# PCBMotores.net
KiCad netlist of a schematic drawn in EAGLE
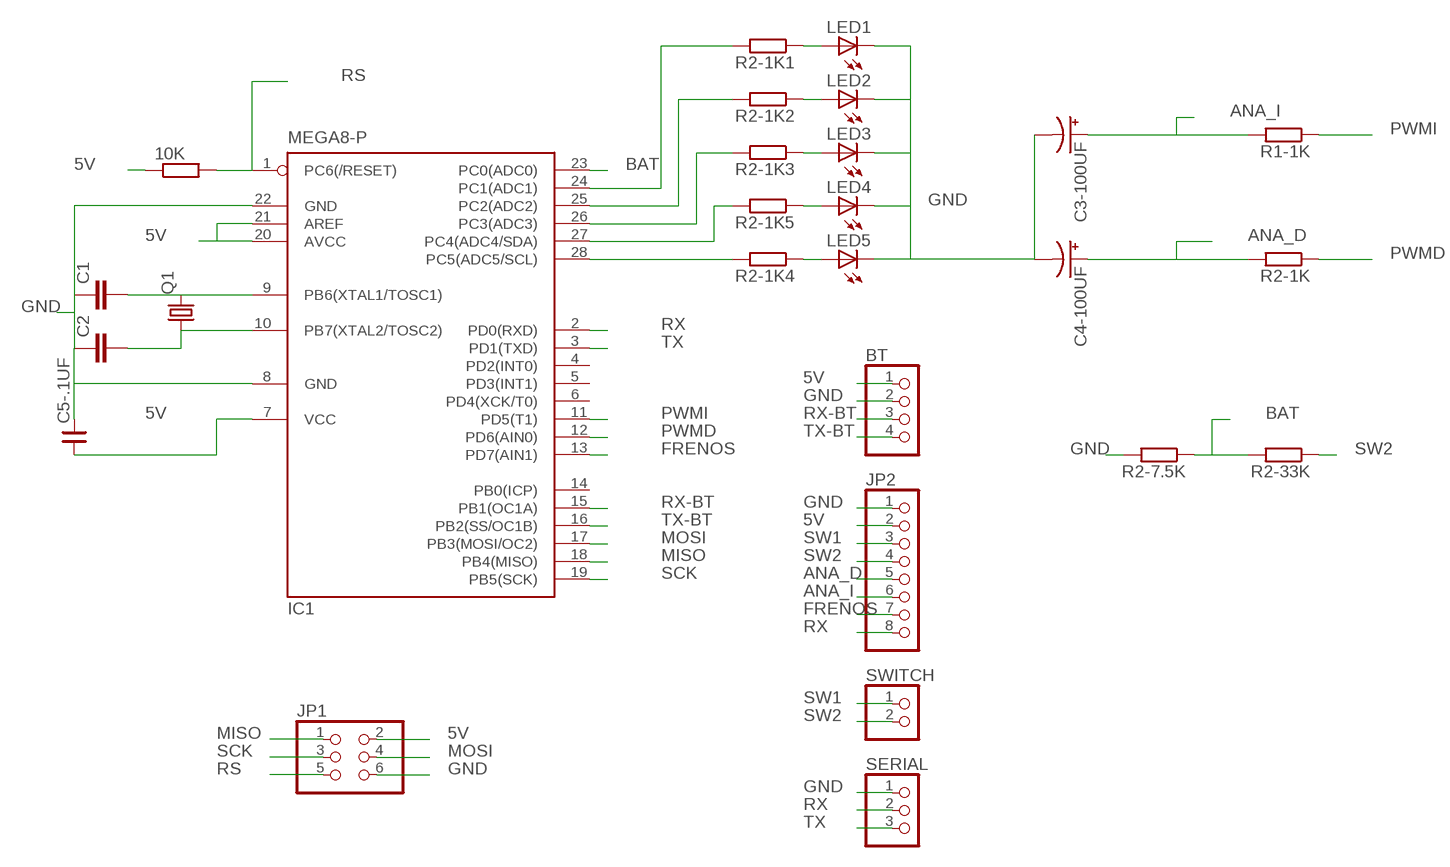
[diagram p0: schematic, sheet 1]

(export (version "E")
  (design (tool "Eeschema 10.0.6"))
  (components
    (comp (ref "10K")
      (value "R-EU_0204/7")
      (footprint "eagle-import:0204_7")
      (libsource (lib "eagle-import") (part "R-EU_0204/7"))
    )
    (comp (ref "BT")
      (value "PINHD-1X4")
      (footprint "eagle-import:1X04")
      (libsource (lib "eagle-import") (part "PINHD-1X4"))
    )
    (comp (ref "C1")
      (value "C2.5/5")
      (footprint "eagle-import:C2.5-5")
      (libsource (lib "eagle-import") (part "C2.5/5"))
    )
    (comp (ref "C2")
      (value "C2.5/5")
      (footprint "eagle-import:C2.5-5")
      (libsource (lib "eagle-import") (part "C2.5/5"))
    )
    (comp (ref "C3-100UF")
      (value "CPOL-USE2-4")
      (footprint "eagle-import:E2-4")
      (libsource (lib "eagle-import") (part "CPOL-USE2-4"))
    )
    (comp (ref "C4-100UF")
      (value "CPOL-USE2-4")
      (footprint "eagle-import:E2-4")
      (libsource (lib "eagle-import") (part "CPOL-USE2-4"))
    )
    (comp (ref "C5-.1UF")
      (value "CNP-C035-055X025")
      (footprint "eagle-import:C035-055X025")
      (libsource (lib "eagle-import") (part "CNP-C035-055X025"))
    )
    (comp (ref "IC1")
      (value "MEGA8-P")
      (footprint "eagle-import:DIL28-3")
      (libsource (lib "eagle-import") (part "MEGA8-P"))
    )
    (comp (ref "JP1")
      (value "PINHD-2X3")
      (footprint "eagle-import:2X03")
      (libsource (lib "eagle-import") (part "PINHD-2X3"))
    )
    (comp (ref "JP2")
      (value "PINHD-1X8")
      (footprint "eagle-import:1X08")
      (libsource (lib "eagle-import") (part "PINHD-1X8"))
    )
    (comp (ref "LED1")
      (value "LED5MM")
      (footprint "eagle-import:LED5MM")
      (libsource (lib "eagle-import") (part "LED5MM"))
    )
    (comp (ref "LED2")
      (value "LED5MM")
      (footprint "eagle-import:LED5MM")
      (libsource (lib "eagle-import") (part "LED5MM"))
    )
    (comp (ref "LED3")
      (value "LED5MM")
      (footprint "eagle-import:LED5MM")
      (libsource (lib "eagle-import") (part "LED5MM"))
    )
    (comp (ref "LED4")
      (value "LED5MM")
      (footprint "eagle-import:LED5MM")
      (libsource (lib "eagle-import") (part "LED5MM"))
    )
    (comp (ref "LED5")
      (value "LED5MM")
      (footprint "eagle-import:LED5MM")
      (libsource (lib "eagle-import") (part "LED5MM"))
    )
    (comp (ref "Q1")
      (value "CRYSTALHC49S")
      (footprint "eagle-import:HC49_S")
      (libsource (lib "eagle-import") (part "CRYSTALHC49S"))
    )
    (comp (ref "R1-1K")
      (value "R-EU_0207/10")
      (footprint "eagle-import:0207_10")
      (libsource (lib "eagle-import") (part "R-EU_0207/10"))
    )
    (comp (ref "R2-1K")
      (value "R-EU_0207/10")
      (footprint "eagle-import:0207_10")
      (libsource (lib "eagle-import") (part "R-EU_0207/10"))
    )
    (comp (ref "R2-1K1")
      (value "R-EU_0207/10")
      (footprint "eagle-import:0207_10")
      (libsource (lib "eagle-import") (part "R-EU_0207/10"))
    )
    (comp (ref "R2-1K2")
      (value "R-EU_0207/10")
      (footprint "eagle-import:0207_10")
      (libsource (lib "eagle-import") (part "R-EU_0207/10"))
    )
    (comp (ref "R2-1K3")
      (value "R-EU_0207/10")
      (footprint "eagle-import:0207_10")
      (libsource (lib "eagle-import") (part "R-EU_0207/10"))
    )
    (comp (ref "R2-1K4")
      (value "R-EU_0207/10")
      (footprint "eagle-import:0207_10")
      (libsource (lib "eagle-import") (part "R-EU_0207/10"))
    )
    (comp (ref "R2-1K5")
      (value "R-EU_0207/10")
      (footprint "eagle-import:0207_10")
      (libsource (lib "eagle-import") (part "R-EU_0207/10"))
    )
    (comp (ref "R2-7.5K")
      (value "R-EU_0207/10")
      (footprint "eagle-import:0207_10")
      (libsource (lib "eagle-import") (part "R-EU_0207/10"))
    )
    (comp (ref "R2-33K")
      (value "R-EU_0207/10")
      (footprint "eagle-import:0207_10")
      (libsource (lib "eagle-import") (part "R-EU_0207/10"))
    )
    (comp (ref "SERIAL")
      (value "PINHD-1X3")
      (footprint "eagle-import:1X03")
      (libsource (lib "eagle-import") (part "PINHD-1X3"))
    )
    (comp (ref "SWITCH")
      (value "PINHD-1X2")
      (footprint "eagle-import:1X02")
      (libsource (lib "eagle-import") (part "PINHD-1X2"))
    )
  )
  (nets
    (net (code "1") (name "/5V") (class "Default")
      (node (ref "10K") (pin "1") (pinfunction "1_1") (pintype "passive"))
      (node (ref "BT") (pin "1") (pinfunction "1_1") (pintype "passive"))
      (node (ref "C5-.1UF") (pin "1") (pinfunction "1_1") (pintype "passive"))
      (node (ref "IC1") (pin "20") (pinfunction "AVCC_20") (pintype "power_in"))
      (node (ref "IC1") (pin "21") (pinfunction "AREF_21") (pintype "passive"))
      (node (ref "IC1") (pin "7") (pinfunction "VCC_7") (pintype "power_in"))
      (node (ref "JP1") (pin "2") (pinfunction "2_2") (pintype "passive"))
      (node (ref "JP2") (pin "2") (pinfunction "2_2") (pintype "passive"))
    )
    (net (code "2") (name "/ANA_D") (class "Default")
      (node (ref "C4-100UF") (pin "+") (pinfunction "+_+") (pintype "passive"))
      (node (ref "JP2") (pin "5") (pinfunction "5_5") (pintype "passive"))
      (node (ref "R2-1K") (pin "2") (pinfunction "2_2") (pintype "passive"))
    )
    (net (code "3") (name "/ANA_I") (class "Default")
      (node (ref "C3-100UF") (pin "+") (pinfunction "+_+") (pintype "passive"))
      (node (ref "JP2") (pin "6") (pinfunction "6_6") (pintype "passive"))
      (node (ref "R1-1K") (pin "2") (pinfunction "2_2") (pintype "passive"))
    )
    (net (code "4") (name "/BAT") (class "Default")
      (node (ref "IC1") (pin "23") (pinfunction "PC0(ADC0)_23") (pintype "bidirectional"))
      (node (ref "R2-33K") (pin "2") (pinfunction "2_2") (pintype "passive"))
      (node (ref "R2-7.5K") (pin "1") (pinfunction "1_1") (pintype "passive"))
    )
    (net (code "5") (name "/FRENOS") (class "Default")
      (node (ref "IC1") (pin "13") (pinfunction "PD7(AIN1)_13") (pintype "bidirectional"))
      (node (ref "JP2") (pin "7") (pinfunction "7_7") (pintype "passive"))
    )
    (net (code "6") (name "/GND") (class "Default")
      (node (ref "BT") (pin "2") (pinfunction "2_2") (pintype "passive"))
      (node (ref "C1") (pin "1") (pinfunction "1_1") (pintype "passive"))
      (node (ref "C2") (pin "1") (pinfunction "1_1") (pintype "passive"))
      (node (ref "C3-100UF") (pin "-") (pinfunction "-_-") (pintype "passive"))
      (node (ref "C4-100UF") (pin "-") (pinfunction "-_-") (pintype "passive"))
      (node (ref "C5-.1UF") (pin "2") (pinfunction "2_2") (pintype "passive"))
      (node (ref "IC1") (pin "22") (pinfunction "GND_22") (pintype "power_in"))
      (node (ref "IC1") (pin "8") (pinfunction "GND_8") (pintype "power_in"))
      (node (ref "JP1") (pin "6") (pinfunction "6_6") (pintype "passive"))
      (node (ref "JP2") (pin "1") (pinfunction "1_1") (pintype "passive"))
      (node (ref "LED1") (pin "K") (pinfunction "C_K") (pintype "passive"))
      (node (ref "LED2") (pin "K") (pinfunction "C_K") (pintype "passive"))
      (node (ref "LED3") (pin "K") (pinfunction "C_K") (pintype "passive"))
      (node (ref "LED4") (pin "K") (pinfunction "C_K") (pintype "passive"))
      (node (ref "LED5") (pin "K") (pinfunction "C_K") (pintype "passive"))
      (node (ref "R2-7.5K") (pin "2") (pinfunction "2_2") (pintype "passive"))
      (node (ref "SERIAL") (pin "1") (pinfunction "1_1") (pintype "passive"))
    )
    (net (code "7") (name "/MISO") (class "Default")
      (node (ref "IC1") (pin "18") (pinfunction "PB4(MISO)_18") (pintype "bidirectional"))
      (node (ref "JP1") (pin "1") (pinfunction "1_1") (pintype "passive"))
    )
    (net (code "8") (name "/MOSI") (class "Default")
      (node (ref "IC1") (pin "17") (pinfunction "PB3(MOSI/OC2)_17") (pintype "bidirectional"))
      (node (ref "JP1") (pin "4") (pinfunction "4_4") (pintype "passive"))
    )
    (net (code "9") (name "/PWMD") (class "Default")
      (node (ref "IC1") (pin "12") (pinfunction "PD6(AIN0)_12") (pintype "bidirectional"))
      (node (ref "R2-1K") (pin "1") (pinfunction "1_1") (pintype "passive"))
    )
    (net (code "10") (name "/PWMI") (class "Default")
      (node (ref "IC1") (pin "11") (pinfunction "PD5(T1)_11") (pintype "bidirectional"))
      (node (ref "R1-1K") (pin "1") (pinfunction "1_1") (pintype "passive"))
    )
    (net (code "11") (name "/RS") (class "Default")
      (node (ref "10K") (pin "2") (pinfunction "2_2") (pintype "passive"))
      (node (ref "IC1") (pin "1") (pinfunction "PC6(/RESET)_1") (pintype "bidirectional"))
      (node (ref "JP1") (pin "5") (pinfunction "5_5") (pintype "passive"))
    )
    (net (code "12") (name "/RX") (class "Default")
      (node (ref "IC1") (pin "2") (pinfunction "PD0(RXD)_2") (pintype "bidirectional"))
      (node (ref "JP2") (pin "8") (pinfunction "8_8") (pintype "passive"))
      (node (ref "SERIAL") (pin "2") (pinfunction "2_2") (pintype "passive"))
    )
    (net (code "13") (name "/RX-BT") (class "Default")
      (node (ref "BT") (pin "3") (pinfunction "3_3") (pintype "passive"))
      (node (ref "IC1") (pin "15") (pinfunction "PB1(OC1A)_15") (pintype "bidirectional"))
    )
    (net (code "14") (name "/SCK") (class "Default")
      (node (ref "IC1") (pin "19") (pinfunction "PB5(SCK)_19") (pintype "bidirectional"))
      (node (ref "JP1") (pin "3") (pinfunction "3_3") (pintype "passive"))
    )
    (net (code "15") (name "/SW1") (class "Default")
      (node (ref "JP2") (pin "3") (pinfunction "3_3") (pintype "passive"))
      (node (ref "SWITCH") (pin "1") (pinfunction "1_1") (pintype "passive"))
    )
    (net (code "16") (name "/SW2") (class "Default")
      (node (ref "JP2") (pin "4") (pinfunction "4_4") (pintype "passive"))
      (node (ref "R2-33K") (pin "1") (pinfunction "1_1") (pintype "passive"))
      (node (ref "SWITCH") (pin "2") (pinfunction "2_2") (pintype "passive"))
    )
    (net (code "17") (name "/TX") (class "Default")
      (node (ref "IC1") (pin "3") (pinfunction "PD1(TXD)_3") (pintype "bidirectional"))
      (node (ref "SERIAL") (pin "3") (pinfunction "3_3") (pintype "passive"))
    )
    (net (code "18") (name "/TX-BT") (class "Default")
      (node (ref "BT") (pin "4") (pinfunction "4_4") (pintype "passive"))
      (node (ref "IC1") (pin "16") (pinfunction "PB2(SS/OC1B)_16") (pintype "bidirectional"))
    )
    (net (code "19") (name "Net-(IC1-PB6(XTAL1{slash}TOSC1))") (class "Default")
      (node (ref "C1") (pin "2") (pinfunction "2_2") (pintype "passive"))
      (node (ref "IC1") (pin "9") (pinfunction "PB6(XTAL1/TOSC1)_9") (pintype "bidirectional"))
      (node (ref "Q1") (pin "2") (pinfunction "2_2") (pintype "passive"))
    )
    (net (code "20") (name "Net-(IC1-PB7(XTAL2{slash}TOSC2))") (class "Default")
      (node (ref "C2") (pin "2") (pinfunction "2_2") (pintype "passive"))
      (node (ref "IC1") (pin "10") (pinfunction "PB7(XTAL2/TOSC2)_10") (pintype "bidirectional"))
      (node (ref "Q1") (pin "1") (pinfunction "1_1") (pintype "passive"))
    )
    (net (code "21") (name "Net-(IC1-PC1(ADC1))") (class "Default")
      (node (ref "IC1") (pin "24") (pinfunction "PC1(ADC1)_24") (pintype "bidirectional"))
      (node (ref "R2-1K1") (pin "2") (pinfunction "2_2") (pintype "passive"))
    )
    (net (code "22") (name "Net-(IC1-PC2(ADC2))") (class "Default")
      (node (ref "IC1") (pin "25") (pinfunction "PC2(ADC2)_25") (pintype "bidirectional"))
      (node (ref "R2-1K2") (pin "2") (pinfunction "2_2") (pintype "passive"))
    )
    (net (code "23") (name "Net-(IC1-PC3(ADC3))") (class "Default")
      (node (ref "IC1") (pin "26") (pinfunction "PC3(ADC3)_26") (pintype "bidirectional"))
      (node (ref "R2-1K3") (pin "2") (pinfunction "2_2") (pintype "passive"))
    )
    (net (code "24") (name "Net-(IC1-PC4(ADC4{slash}SDA))") (class "Default")
      (node (ref "IC1") (pin "27") (pinfunction "PC4(ADC4/SDA)_27") (pintype "bidirectional"))
      (node (ref "R2-1K5") (pin "2") (pinfunction "2_2") (pintype "passive"))
    )
    (net (code "25") (name "Net-(IC1-PC5(ADC5{slash}SCL))") (class "Default")
      (node (ref "IC1") (pin "28") (pinfunction "PC5(ADC5/SCL)_28") (pintype "bidirectional"))
      (node (ref "R2-1K4") (pin "2") (pinfunction "2_2") (pintype "passive"))
    )
    (net (code "26") (name "Net-(LED1-PadA)") (class "Default")
      (node (ref "LED1") (pin "A") (pinfunction "A_A") (pintype "passive"))
      (node (ref "R2-1K1") (pin "1") (pinfunction "1_1") (pintype "passive"))
    )
    (net (code "27") (name "Net-(LED2-PadA)") (class "Default")
      (node (ref "LED2") (pin "A") (pinfunction "A_A") (pintype "passive"))
      (node (ref "R2-1K2") (pin "1") (pinfunction "1_1") (pintype "passive"))
    )
    (net (code "28") (name "Net-(LED3-PadA)") (class "Default")
      (node (ref "LED3") (pin "A") (pinfunction "A_A") (pintype "passive"))
      (node (ref "R2-1K3") (pin "1") (pinfunction "1_1") (pintype "passive"))
    )
    (net (code "29") (name "Net-(LED4-PadA)") (class "Default")
      (node (ref "LED4") (pin "A") (pinfunction "A_A") (pintype "passive"))
      (node (ref "R2-1K5") (pin "1") (pinfunction "1_1") (pintype "passive"))
    )
    (net (code "30") (name "Net-(LED5-PadA)") (class "Default")
      (node (ref "LED5") (pin "A") (pinfunction "A_A") (pintype "passive"))
      (node (ref "R2-1K4") (pin "1") (pinfunction "1_1") (pintype "passive"))
    )
    (net (code "31") (name "unconnected-(IC1-PB0(ICP)-Pad14)") (class "Default")
      (node (ref "IC1") (pin "14") (pinfunction "PB0(ICP)_14") (pintype "bidirectional"))
    )
    (net (code "32") (name "unconnected-(IC1-PD2(INT0)-Pad4)") (class "Default")
      (node (ref "IC1") (pin "4") (pinfunction "PD2(INT0)_4") (pintype "bidirectional"))
    )
    (net (code "33") (name "unconnected-(IC1-PD3(INT1)-Pad5)") (class "Default")
      (node (ref "IC1") (pin "5") (pinfunction "PD3(INT1)_5") (pintype "bidirectional"))
    )
    (net (code "34") (name "unconnected-(IC1-PD4(XCK{slash}T0)-Pad6)") (class "Default")
      (node (ref "IC1") (pin "6") (pinfunction "PD4(XCK/T0)_6") (pintype "bidirectional"))
    )
  )
)
